# RasPi_Hat_Temp.net
KiCad netlist of a schematic drawn in Altium Designer
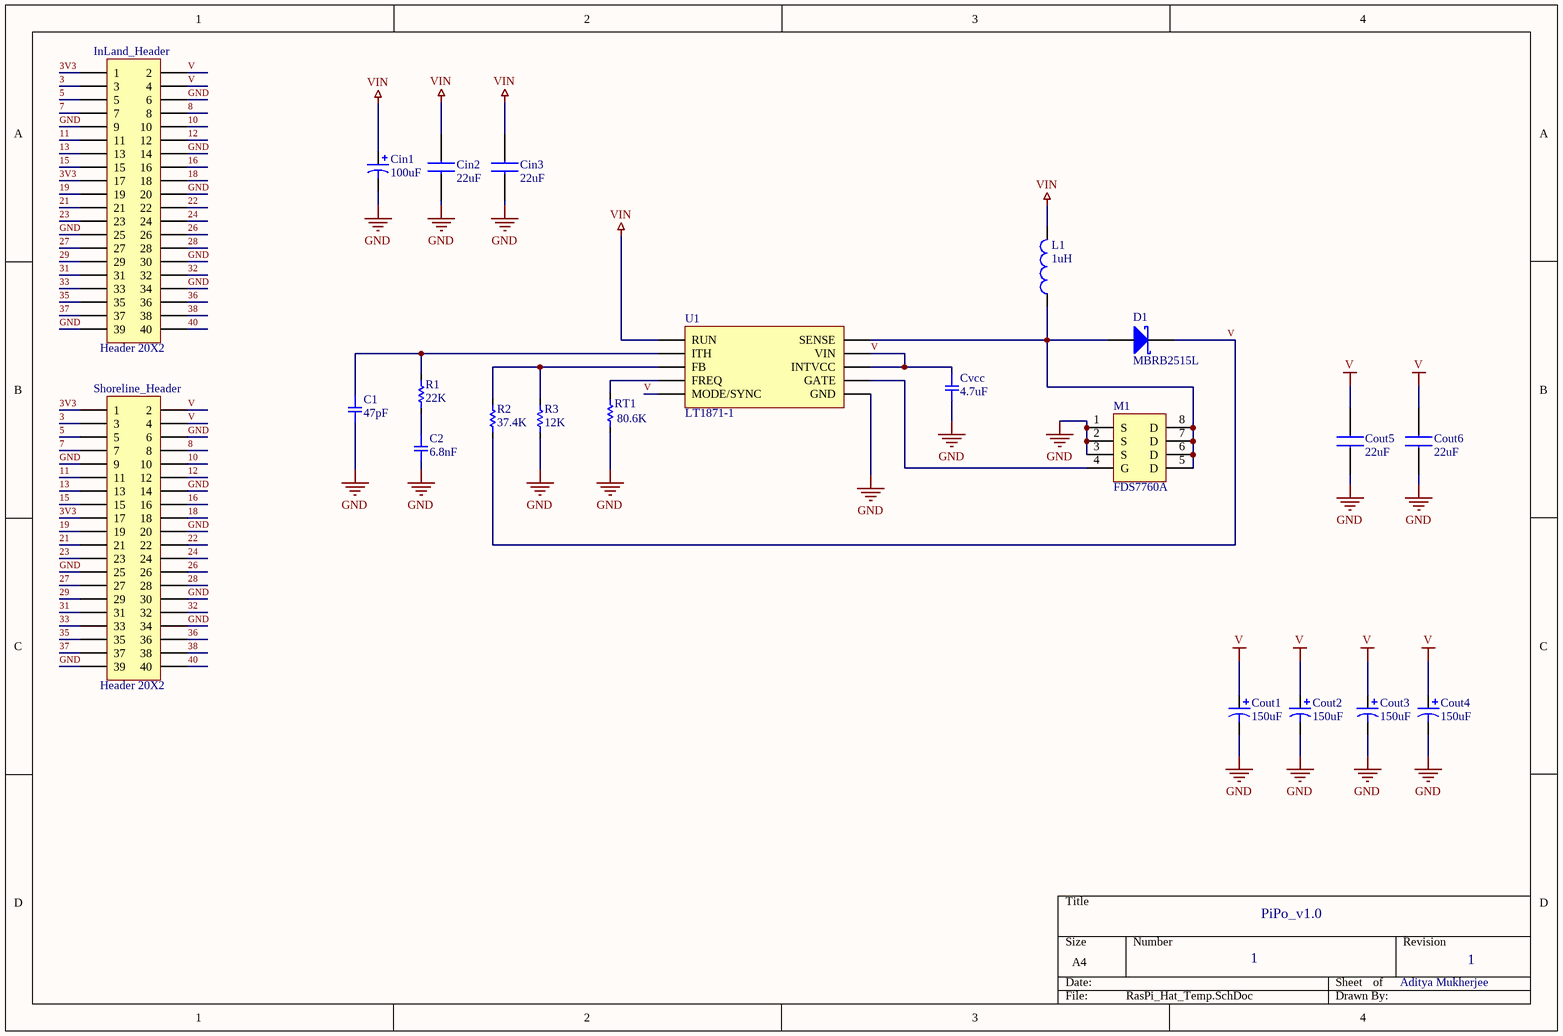
[diagram p0: RasPi_Hat_Temp.SchDoc]

(export (version "E")
  (design (tool "Eeschema 10.0.6"))
  (components
    (comp (ref "C1")
      (value "47pF")
      (footprint "SMD-0805C")
      (description "CAP CER 10000PF 250V X7T 0805")
      (fields
        (field (name "DIGI-KEY PART NUMBER") "490-13986-1-ND")
        (field (name "PART NUMBER") "GC321AD72E103KX01D")
      )
      (libsource (lib "capacitor_murata_0805") (part "GC321AD72E103KX01D"))
    )
    (comp (ref "C2")
      (value "6.8nF")
      (footprint "SMD-0603C")
      (description "CAP CER 0.1UF 16V X7R 0603")
      (fields
        (field (name "DIGI-KEY PART NUMBER") "490-5796-1-ND")
        (field (name "PART NUMBER") "GCJ188R71C104KA01D")
      )
      (libsource (lib "capacitor_murata_0603") (part "GCJ188R71C104KA01D"))
    )
    (comp (ref "Cin1")
      (value "100uF")
      (footprint "TPSA226K006T0300")
      (description "1206_TANTALUM")
      (libsource (lib "AVX_1206_Tantalum") (part "Component_1"))
    )
    (comp (ref "Cin2")
      (value "22uF")
      (footprint "PCBComponent_1")
      (libsource (lib "tiyo_cap") (part "Component_1"))
    )
    (comp (ref "Cin3")
      (value "22uF")
      (footprint "PCBComponent_1")
      (libsource (lib "tiyo_cap") (part "Component_1"))
    )
    (comp (ref "Cout1")
      (value "150uF")
      (footprint "EEF-CX0J151R")
      (libsource (lib "Panasonic_spcap") (part "Component_1"))
    )
    (comp (ref "Cout2")
      (value "150uF")
      (footprint "EEF-CX0J151R")
      (libsource (lib "Panasonic_spcap") (part "Component_1"))
    )
    (comp (ref "Cout3")
      (value "150uF")
      (footprint "EEF-CX0J151R")
      (libsource (lib "Panasonic_spcap") (part "Component_1"))
    )
    (comp (ref "Cout4")
      (value "150uF")
      (footprint "EEF-CX0J151R")
      (libsource (lib "Panasonic_spcap") (part "Component_1"))
    )
    (comp (ref "Cout5")
      (value "22uF")
      (footprint "PCBComponent_1")
      (libsource (lib "tiyo_cap") (part "Component_1"))
    )
    (comp (ref "Cout6")
      (value "22uF")
      (footprint "PCBComponent_1")
      (libsource (lib "tiyo_cap") (part "Component_1"))
    )
    (comp (ref "Cvcc")
      (value "4.7uF")
      (footprint "SMD-0805C")
      (description "CAP CER 10000PF 250V X5R 0805")
      (fields
        (field (name "DIGI-KEY PART NUMBER") "490-13986-1-ND")
        (field (name "PART NUMBER") "GC321AD72E103KX01D")
      )
      (libsource (lib "capacitor_murata_0805") (part "GC321AD72E103KX01D"))
    )
    (comp (ref "D1")
      (value "MBRB2515L")
      (footprint "MBRB2515L")
      (libsource (lib "MBRB2515L") (part "Component_1"))
    )
    (comp (ref "InLand_Header")
      (value "Header 20X2")
      (footprint "HDR2X20")
      (description "Header, 20-Pin, Dual row")
      (fields (field (name "PUBLISHER") "Altium Limited"))
      (libsource (lib "Miscellaneous Connectors") (part "Header 20X2"))
    )
    (comp (ref "L1")
      (value "1uH")
      (footprint "PCBComponent_1")
      (libsource (lib "SMD POWER INDUCTORS") (part "Component_1"))
    )
    (comp (ref "M1")
      (value "FDS7760A")
      (footprint "FDS7760A")
      (libsource (lib "FDS7760A") (part "Component_1"))
    )
    (comp (ref "R1") (value "22K") (footprint "Resistor_0805") (libsource (lib "res") (part "Component_1")))
    (comp (ref "R2") (value "37.4K") (footprint "Resistor_0805") (libsource (lib "res") (part "Component_1")))
    (comp (ref "R3") (value "12K") (footprint "Resistor_0805") (libsource (lib "res") (part "Component_1")))
    (comp (ref "RT1")
      (value "80.6K")
      (footprint "Resistor_0805")
      (libsource (lib "res") (part "Component_1"))
    )
    (comp (ref "Shoreline_Header")
      (value "Header 20X2")
      (footprint "HDR2X20")
      (description "Header, 20-Pin, Dual row")
      (fields (field (name "PUBLISHER") "Altium Limited"))
      (libsource (lib "Miscellaneous Connectors") (part "Header 20X2"))
    )
    (comp (ref "U1")
      (value "LT1871-1")
      (footprint "LTC1871-1")
      (libsource (lib "LT1871-1") (part "Component_1"))
    )
  )
  (nets
    (net (code "1") (name "/3") (class "Default")
      (node (ref "InLand_Header") (pin "3") (pinfunction "3_3") (pintype "passive"))
      (node (ref "Shoreline_Header") (pin "3") (pinfunction "3_3") (pintype "passive"))
    )
    (net (code "2") (name "/3V3") (class "Default")
      (node (ref "InLand_Header") (pin "1") (pinfunction "1_1") (pintype "passive"))
      (node (ref "InLand_Header") (pin "17") (pinfunction "17_17") (pintype "passive"))
      (node (ref "Shoreline_Header") (pin "1") (pinfunction "1_1") (pintype "passive"))
      (node (ref "Shoreline_Header") (pin "17") (pinfunction "17_17") (pintype "passive"))
    )
    (net (code "3") (name "/5") (class "Default")
      (node (ref "InLand_Header") (pin "5") (pinfunction "5_5") (pintype "passive"))
      (node (ref "Shoreline_Header") (pin "5") (pinfunction "5_5") (pintype "passive"))
    )
    (net (code "4") (name "/7") (class "Default")
      (node (ref "InLand_Header") (pin "7") (pinfunction "7_7") (pintype "passive"))
      (node (ref "Shoreline_Header") (pin "7") (pinfunction "7_7") (pintype "passive"))
    )
    (net (code "5") (name "/8") (class "Default")
      (node (ref "InLand_Header") (pin "8") (pinfunction "8_8") (pintype "passive"))
      (node (ref "Shoreline_Header") (pin "8") (pinfunction "8_8") (pintype "passive"))
    )
    (net (code "6") (name "/10") (class "Default")
      (node (ref "InLand_Header") (pin "10") (pinfunction "10_10") (pintype "passive"))
      (node (ref "Shoreline_Header") (pin "10") (pinfunction "10_10") (pintype "passive"))
    )
    (net (code "7") (name "/11") (class "Default")
      (node (ref "InLand_Header") (pin "11") (pinfunction "11_11") (pintype "passive"))
      (node (ref "Shoreline_Header") (pin "11") (pinfunction "11_11") (pintype "passive"))
    )
    (net (code "8") (name "/12") (class "Default")
      (node (ref "InLand_Header") (pin "12") (pinfunction "12_12") (pintype "passive"))
      (node (ref "Shoreline_Header") (pin "12") (pinfunction "12_12") (pintype "passive"))
    )
    (net (code "9") (name "/13") (class "Default")
      (node (ref "InLand_Header") (pin "13") (pinfunction "13_13") (pintype "passive"))
      (node (ref "Shoreline_Header") (pin "13") (pinfunction "13_13") (pintype "passive"))
    )
    (net (code "10") (name "/15") (class "Default")
      (node (ref "InLand_Header") (pin "15") (pinfunction "15_15") (pintype "passive"))
      (node (ref "Shoreline_Header") (pin "15") (pinfunction "15_15") (pintype "passive"))
    )
    (net (code "11") (name "/16") (class "Default")
      (node (ref "InLand_Header") (pin "16") (pinfunction "16_16") (pintype "passive"))
      (node (ref "Shoreline_Header") (pin "16") (pinfunction "16_16") (pintype "passive"))
    )
    (net (code "12") (name "/18") (class "Default")
      (node (ref "InLand_Header") (pin "18") (pinfunction "18_18") (pintype "passive"))
      (node (ref "Shoreline_Header") (pin "18") (pinfunction "18_18") (pintype "passive"))
    )
    (net (code "13") (name "/19") (class "Default")
      (node (ref "InLand_Header") (pin "19") (pinfunction "19_19") (pintype "passive"))
      (node (ref "Shoreline_Header") (pin "19") (pinfunction "19_19") (pintype "passive"))
    )
    (net (code "14") (name "/21") (class "Default")
      (node (ref "InLand_Header") (pin "21") (pinfunction "21_21") (pintype "passive"))
      (node (ref "Shoreline_Header") (pin "21") (pinfunction "21_21") (pintype "passive"))
    )
    (net (code "15") (name "/22") (class "Default")
      (node (ref "InLand_Header") (pin "22") (pinfunction "22_22") (pintype "passive"))
      (node (ref "Shoreline_Header") (pin "22") (pinfunction "22_22") (pintype "passive"))
    )
    (net (code "16") (name "/23") (class "Default")
      (node (ref "InLand_Header") (pin "23") (pinfunction "23_23") (pintype "passive"))
      (node (ref "Shoreline_Header") (pin "23") (pinfunction "23_23") (pintype "passive"))
    )
    (net (code "17") (name "/24") (class "Default")
      (node (ref "InLand_Header") (pin "24") (pinfunction "24_24") (pintype "passive"))
      (node (ref "Shoreline_Header") (pin "24") (pinfunction "24_24") (pintype "passive"))
    )
    (net (code "18") (name "/26") (class "Default")
      (node (ref "InLand_Header") (pin "26") (pinfunction "26_26") (pintype "passive"))
      (node (ref "Shoreline_Header") (pin "26") (pinfunction "26_26") (pintype "passive"))
    )
    (net (code "19") (name "/27") (class "Default")
      (node (ref "InLand_Header") (pin "27") (pinfunction "27_27") (pintype "passive"))
      (node (ref "Shoreline_Header") (pin "27") (pinfunction "27_27") (pintype "passive"))
    )
    (net (code "20") (name "/28") (class "Default")
      (node (ref "InLand_Header") (pin "28") (pinfunction "28_28") (pintype "passive"))
      (node (ref "Shoreline_Header") (pin "28") (pinfunction "28_28") (pintype "passive"))
    )
    (net (code "21") (name "/29") (class "Default")
      (node (ref "InLand_Header") (pin "29") (pinfunction "29_29") (pintype "passive"))
      (node (ref "Shoreline_Header") (pin "29") (pinfunction "29_29") (pintype "passive"))
    )
    (net (code "22") (name "/31") (class "Default")
      (node (ref "InLand_Header") (pin "31") (pinfunction "31_31") (pintype "passive"))
      (node (ref "Shoreline_Header") (pin "31") (pinfunction "31_31") (pintype "passive"))
    )
    (net (code "23") (name "/32") (class "Default")
      (node (ref "InLand_Header") (pin "32") (pinfunction "32_32") (pintype "passive"))
      (node (ref "Shoreline_Header") (pin "32") (pinfunction "32_32") (pintype "passive"))
    )
    (net (code "24") (name "/33") (class "Default")
      (node (ref "InLand_Header") (pin "33") (pinfunction "33_33") (pintype "passive"))
      (node (ref "Shoreline_Header") (pin "33") (pinfunction "33_33") (pintype "passive"))
    )
    (net (code "25") (name "/35") (class "Default")
      (node (ref "InLand_Header") (pin "35") (pinfunction "35_35") (pintype "passive"))
      (node (ref "Shoreline_Header") (pin "35") (pinfunction "35_35") (pintype "passive"))
    )
    (net (code "26") (name "/36") (class "Default")
      (node (ref "InLand_Header") (pin "36") (pinfunction "36_36") (pintype "passive"))
      (node (ref "Shoreline_Header") (pin "36") (pinfunction "36_36") (pintype "passive"))
    )
    (net (code "27") (name "/37") (class "Default")
      (node (ref "InLand_Header") (pin "37") (pinfunction "37_37") (pintype "passive"))
      (node (ref "Shoreline_Header") (pin "37") (pinfunction "37_37") (pintype "passive"))
    )
    (net (code "28") (name "/38") (class "Default")
      (node (ref "InLand_Header") (pin "38") (pinfunction "38_38") (pintype "passive"))
      (node (ref "Shoreline_Header") (pin "38") (pinfunction "38_38") (pintype "passive"))
    )
    (net (code "29") (name "/40") (class "Default")
      (node (ref "InLand_Header") (pin "40") (pinfunction "40_40") (pintype "passive"))
      (node (ref "Shoreline_Header") (pin "40") (pinfunction "40_40") (pintype "passive"))
    )
    (net (code "30") (name "GND") (class "Default")
      (node (ref "C1") (pin "2") (pinfunction "2_2") (pintype "passive"))
      (node (ref "C2") (pin "2") (pinfunction "2_2") (pintype "passive"))
      (node (ref "Cin1") (pin "2") (pinfunction "2_2") (pintype "passive"))
      (node (ref "Cin2") (pin "1") (pinfunction "1_1") (pintype "passive"))
      (node (ref "Cin3") (pin "1") (pinfunction "1_1") (pintype "passive"))
      (node (ref "Cout1") (pin "1") (pinfunction "1_1") (pintype "passive"))
      (node (ref "Cout2") (pin "1") (pinfunction "1_1") (pintype "passive"))
      (node (ref "Cout3") (pin "1") (pinfunction "1_1") (pintype "passive"))
      (node (ref "Cout4") (pin "1") (pinfunction "1_1") (pintype "passive"))
      (node (ref "Cout5") (pin "1") (pinfunction "1_1") (pintype "passive"))
      (node (ref "Cout6") (pin "1") (pinfunction "1_1") (pintype "passive"))
      (node (ref "Cvcc") (pin "2") (pinfunction "2_2") (pintype "passive"))
      (node (ref "InLand_Header") (pin "14") (pinfunction "14_14") (pintype "passive"))
      (node (ref "InLand_Header") (pin "20") (pinfunction "20_20") (pintype "passive"))
      (node (ref "InLand_Header") (pin "25") (pinfunction "25_25") (pintype "passive"))
      (node (ref "InLand_Header") (pin "30") (pinfunction "30_30") (pintype "passive"))
      (node (ref "InLand_Header") (pin "34") (pinfunction "34_34") (pintype "passive"))
      (node (ref "InLand_Header") (pin "39") (pinfunction "39_39") (pintype "passive"))
      (node (ref "InLand_Header") (pin "6") (pinfunction "6_6") (pintype "passive"))
      (node (ref "InLand_Header") (pin "9") (pinfunction "9_9") (pintype "passive"))
      (node (ref "M1") (pin "1") (pinfunction "S_1") (pintype "passive"))
      (node (ref "M1") (pin "2") (pinfunction "S_2") (pintype "passive"))
      (node (ref "M1") (pin "3") (pinfunction "S_3") (pintype "passive"))
      (node (ref "R3") (pin "1") (pinfunction "1_1") (pintype "passive"))
      (node (ref "RT1") (pin "1") (pinfunction "1_1") (pintype "passive"))
      (node (ref "Shoreline_Header") (pin "14") (pinfunction "14_14") (pintype "passive"))
      (node (ref "Shoreline_Header") (pin "20") (pinfunction "20_20") (pintype "passive"))
      (node (ref "Shoreline_Header") (pin "25") (pinfunction "25_25") (pintype "passive"))
      (node (ref "Shoreline_Header") (pin "30") (pinfunction "30_30") (pintype "passive"))
      (node (ref "Shoreline_Header") (pin "34") (pinfunction "34_34") (pintype "passive"))
      (node (ref "Shoreline_Header") (pin "39") (pinfunction "39_39") (pintype "passive"))
      (node (ref "Shoreline_Header") (pin "6") (pinfunction "6_6") (pintype "passive"))
      (node (ref "Shoreline_Header") (pin "9") (pinfunction "9_9") (pintype "passive"))
      (node (ref "U1") (pin "6") (pinfunction "GND_6") (pintype "passive"))
    )
    (net (code "31") (name "Net-(C2-Pad1)") (class "Default")
      (node (ref "C2") (pin "1") (pinfunction "1_1") (pintype "passive"))
      (node (ref "R1") (pin "1") (pinfunction "1_1") (pintype "passive"))
    )
    (net (code "32") (name "Net-(D1-A)") (class "Default")
      (node (ref "D1") (pin "3") (pinfunction "A_3") (pintype "passive"))
      (node (ref "L1") (pin "1") (pinfunction "1_1") (pintype "passive"))
      (node (ref "M1") (pin "5") (pinfunction "D_5") (pintype "passive"))
      (node (ref "M1") (pin "6") (pinfunction "D_6") (pintype "passive"))
      (node (ref "M1") (pin "7") (pinfunction "D_7") (pintype "passive"))
      (node (ref "M1") (pin "8") (pinfunction "D_8") (pintype "passive"))
      (node (ref "U1") (pin "10") (pinfunction "SENSE_10") (pintype "passive"))
    )
    (net (code "33") (name "Net-(M1-G)") (class "Default")
      (node (ref "M1") (pin "4") (pinfunction "G_4") (pintype "passive"))
      (node (ref "U1") (pin "7") (pinfunction "GATE_7") (pintype "passive"))
    )
    (net (code "34") (name "Net-(U1-FB)") (class "Default")
      (node (ref "R2") (pin "2") (pinfunction "2_2") (pintype "passive"))
      (node (ref "R3") (pin "2") (pinfunction "2_2") (pintype "passive"))
      (node (ref "U1") (pin "3") (pinfunction "FB_3") (pintype "passive"))
    )
    (net (code "35") (name "Net-(U1-FREQ)") (class "Default")
      (node (ref "RT1") (pin "2") (pinfunction "2_2") (pintype "passive"))
      (node (ref "U1") (pin "4") (pinfunction "FREQ_4") (pintype "passive"))
    )
    (net (code "36") (name "Net-(U1-ITH)") (class "Default")
      (node (ref "C1") (pin "1") (pinfunction "1_1") (pintype "passive"))
      (node (ref "R1") (pin "2") (pinfunction "2_2") (pintype "passive"))
      (node (ref "U1") (pin "2") (pinfunction "ITH_2") (pintype "passive"))
    )
    (net (code "37") (name "V") (class "Default")
      (node (ref "Cout1") (pin "2") (pinfunction "2_2") (pintype "passive"))
      (node (ref "Cout2") (pin "2") (pinfunction "2_2") (pintype "passive"))
      (node (ref "Cout3") (pin "2") (pinfunction "2_2") (pintype "passive"))
      (node (ref "Cout4") (pin "2") (pinfunction "2_2") (pintype "passive"))
      (node (ref "Cout5") (pin "2") (pinfunction "2_2") (pintype "passive"))
      (node (ref "Cout6") (pin "2") (pinfunction "2_2") (pintype "passive"))
      (node (ref "Cvcc") (pin "1") (pinfunction "1_1") (pintype "passive"))
      (node (ref "D1") (pin "4") (pinfunction "K_4") (pintype "passive"))
      (node (ref "InLand_Header") (pin "2") (pinfunction "2_2") (pintype "passive"))
      (node (ref "InLand_Header") (pin "4") (pinfunction "4_4") (pintype "passive"))
      (node (ref "R2") (pin "1") (pinfunction "1_1") (pintype "passive"))
      (node (ref "Shoreline_Header") (pin "2") (pinfunction "2_2") (pintype "passive"))
      (node (ref "Shoreline_Header") (pin "4") (pinfunction "4_4") (pintype "passive"))
      (node (ref "U1") (pin "5") (pinfunction "MODE/SYNC_5") (pintype "passive"))
      (node (ref "U1") (pin "8") (pinfunction "INTVCC_8") (pintype "passive"))
      (node (ref "U1") (pin "9") (pinfunction "VIN_9") (pintype "passive"))
    )
    (net (code "38") (name "VIN") (class "Default")
      (node (ref "Cin1") (pin "1") (pinfunction "1_1") (pintype "passive"))
      (node (ref "Cin2") (pin "2") (pinfunction "2_2") (pintype "passive"))
      (node (ref "Cin3") (pin "2") (pinfunction "2_2") (pintype "passive"))
      (node (ref "L1") (pin "2") (pinfunction "2_2") (pintype "passive"))
      (node (ref "U1") (pin "1") (pinfunction "RUN_1") (pintype "passive"))
    )
  )
)
